# 13_BOOT_SELECT.net
KiCad netlist of a schematic drawn in Altium Designer
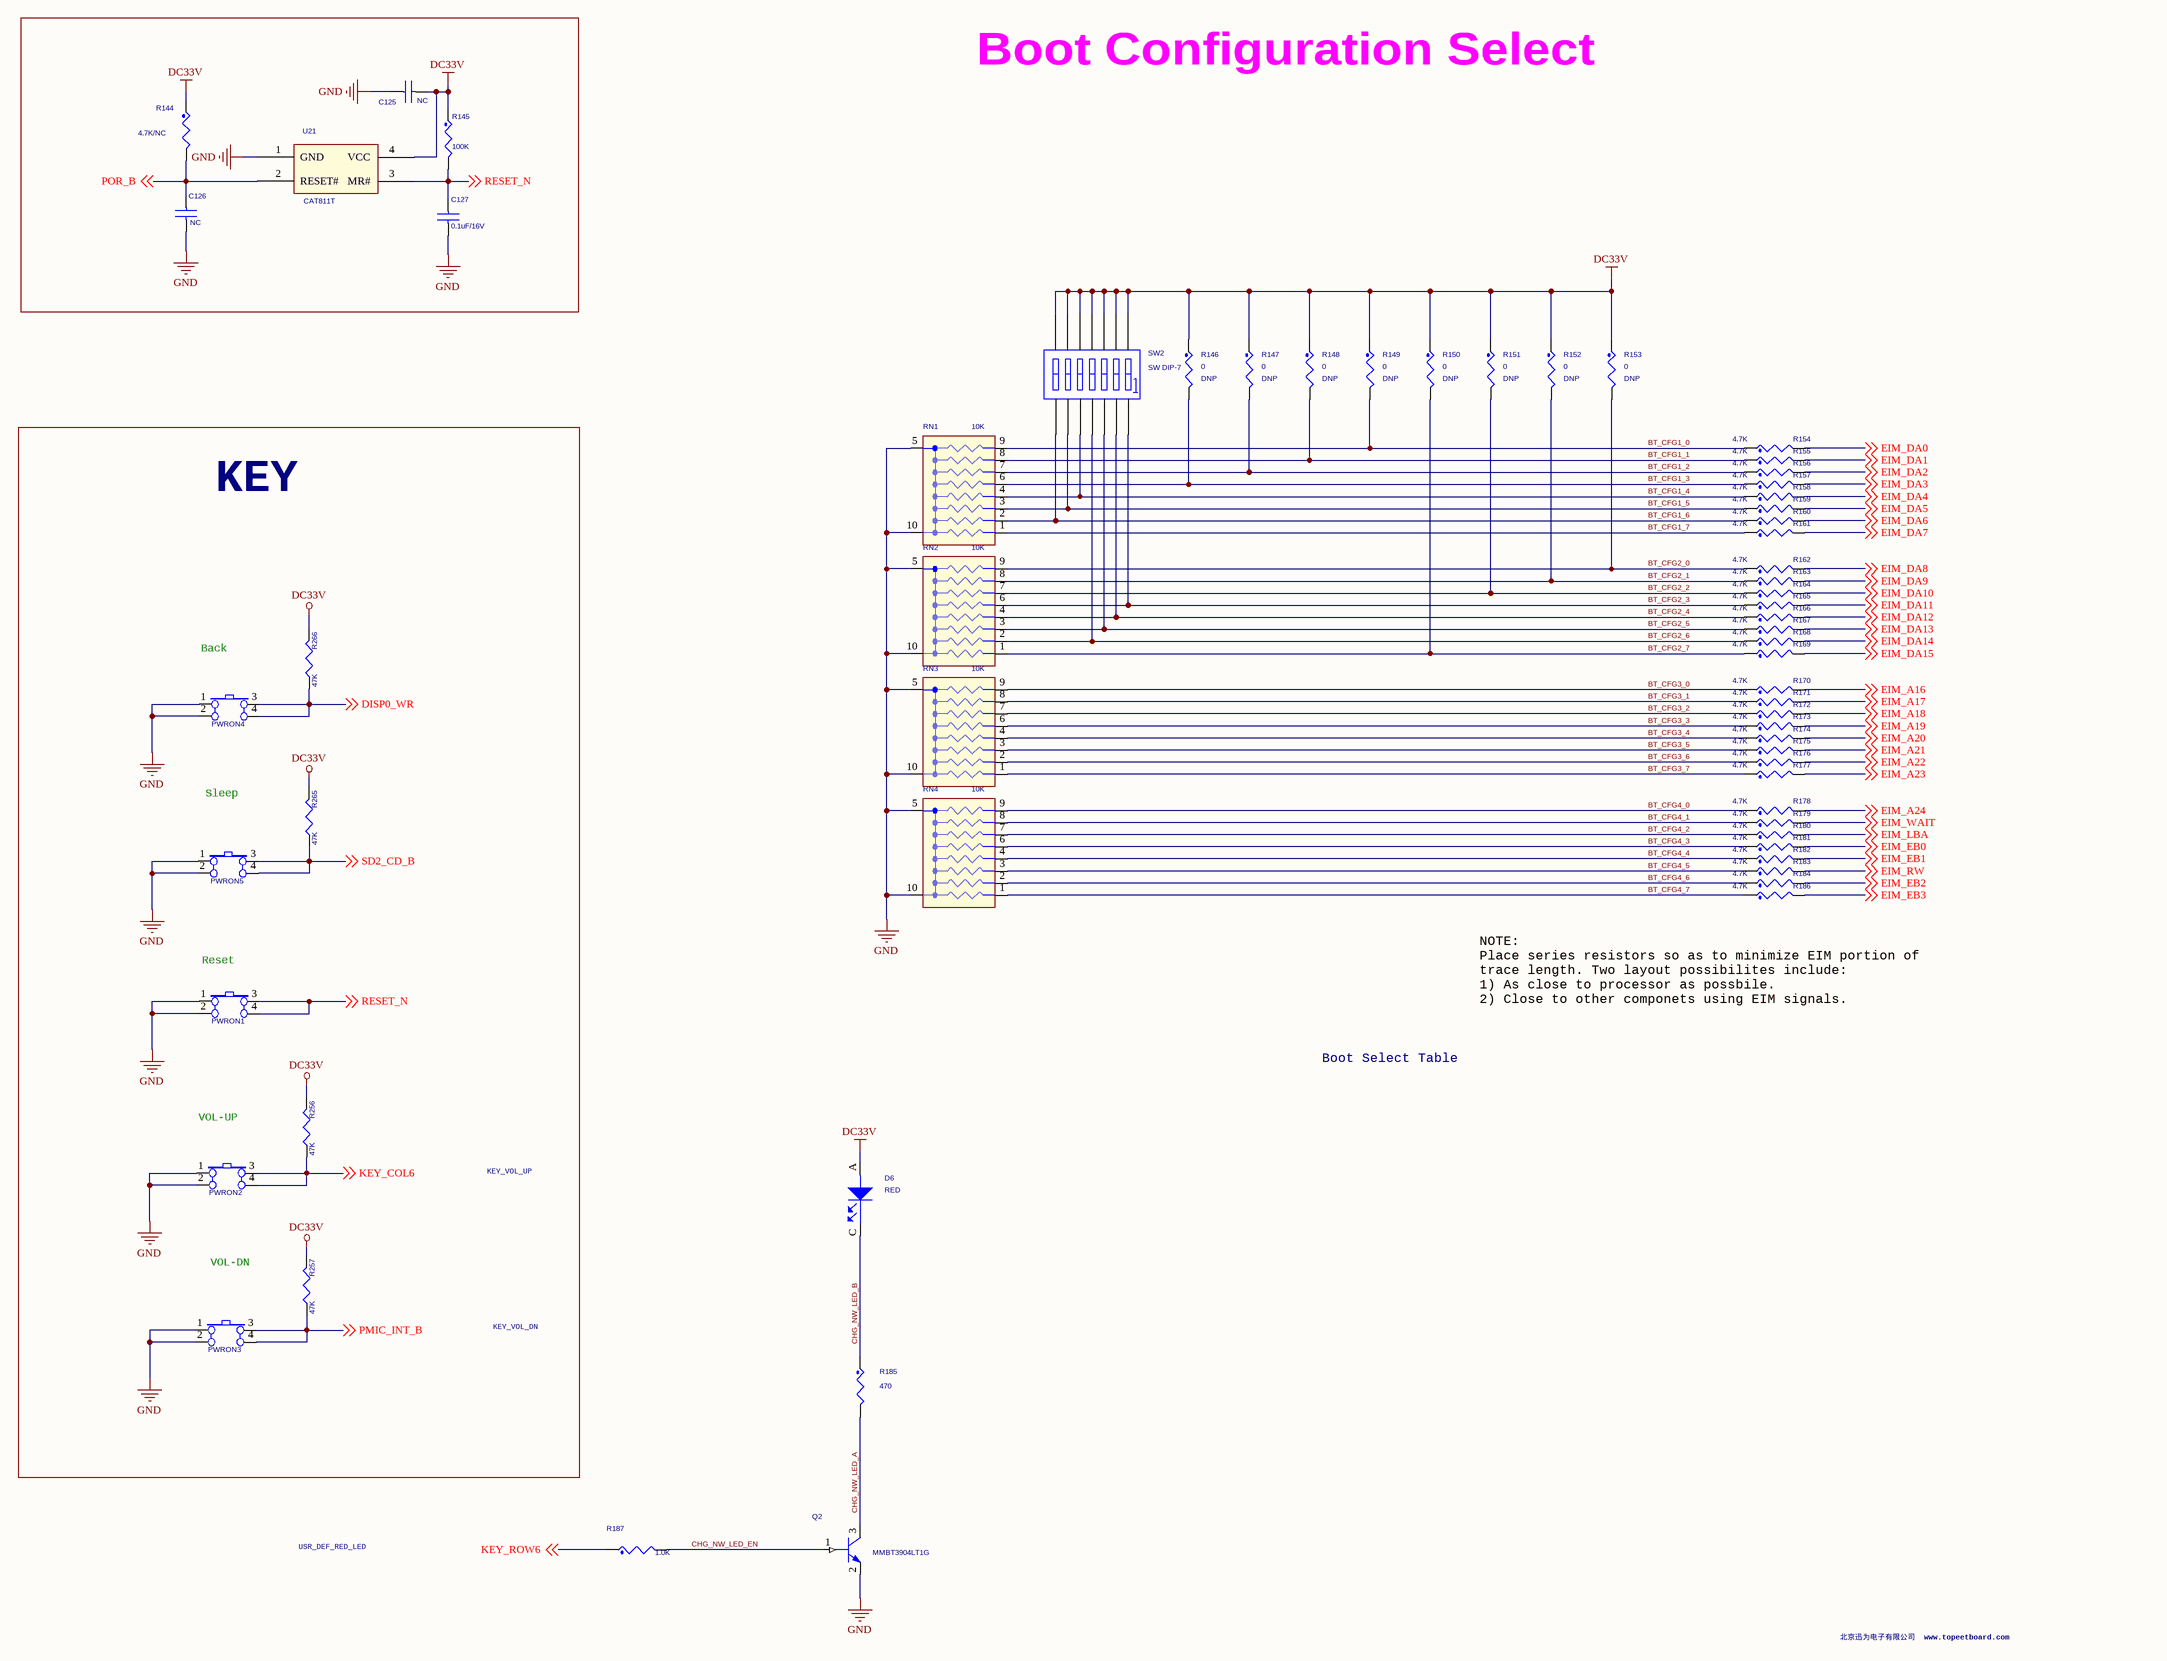
[diagram p0: 13 BOOT SELECT.SchDoc]

(export (version "E")
  (design (tool "Eeschema 10.0.6"))
  (components
    (comp (ref "C125") (value "NC") (footprint "C0603") (libsource (lib "*") (part "C0603_0_Dup1")))
    (comp (ref "C126") (value "NC") (footprint "C0603") (libsource (lib "*") (part "C0603_0_Dup1")))
    (comp (ref "C127") (value "0.1uF/16V") (footprint "C0603") (libsource (lib "*") (part "C0603_0_Dup1")))
    (comp (ref "D6")
      (value "RED")
      (description "LED ULTRA BRIGHT RED SGL 30MA 0603")
      (libsource (lib "*") (part "LED"))
    )
    (comp (ref "PWRON1")
      (value "SW-TACT(RED)_1105S")
      (footprint "SW-TACT")
      (libsource (lib "*") (part "SW-TACT"))
    )
    (comp (ref "PWRON2")
      (value "SW-TACT(RED)_1105S")
      (footprint "SW-TACT")
      (libsource (lib "*") (part "SW-TACT"))
    )
    (comp (ref "PWRON3")
      (value "SW-TACT(RED)_1105S")
      (footprint "SW-TACT")
      (libsource (lib "*") (part "SW-TACT"))
    )
    (comp (ref "PWRON4")
      (value "SW-TACT(RED)_1105S")
      (footprint "SW-TACT")
      (libsource (lib "*") (part "SW-TACT"))
    )
    (comp (ref "PWRON5")
      (value "SW-TACT(RED)_1105S")
      (footprint "SW-TACT")
      (libsource (lib "*") (part "SW-TACT"))
    )
    (comp (ref "Q2")
      (value "MMBT3904LT1G")
      (description "TRAN NPN GEN 200MA 40V SOT-23")
      (libsource (lib "*") (part "NPN"))
    )
    (comp (ref "R144")
      (value "4.7K/NC")
      (description "RES MF 470 OHM 1/10W 1% 0603")
      (fields (field (name "TOLERANCE") "1%"))
      (libsource (lib "*") (part "RES_Dup1"))
    )
    (comp (ref "R145")
      (value "100K")
      (description "RES MF 470 OHM 1/10W 1% 0603")
      (fields (field (name "TOLERANCE") "1%"))
      (libsource (lib "*") (part "RES_Dup1"))
    )
    (comp (ref "R146")
      (value "0")
      (description "RES MF ZERO OHM 1/10W -- 0402")
      (fields (field (name "ASSY_OPT") "DNP"))
      (libsource (lib "*") (part "RES_Dup1"))
    )
    (comp (ref "R147")
      (value "0")
      (description "RES MF ZERO OHM 1/10W -- 0402")
      (fields (field (name "ASSY_OPT") "DNP"))
      (libsource (lib "*") (part "RES_Dup1"))
    )
    (comp (ref "R148")
      (value "0")
      (description "RES MF ZERO OHM 1/10W -- 0402")
      (fields (field (name "ASSY_OPT") "DNP"))
      (libsource (lib "*") (part "RES_Dup1"))
    )
    (comp (ref "R149")
      (value "0")
      (description "RES MF ZERO OHM 1/10W -- 0402")
      (fields (field (name "ASSY_OPT") "DNP"))
      (libsource (lib "*") (part "RES_Dup1"))
    )
    (comp (ref "R150")
      (value "0")
      (description "RES MF ZERO OHM 1/10W -- 0402")
      (fields (field (name "ASSY_OPT") "DNP"))
      (libsource (lib "*") (part "RES_Dup1"))
    )
    (comp (ref "R151")
      (value "0")
      (description "RES MF ZERO OHM 1/10W -- 0402")
      (fields (field (name "ASSY_OPT") "DNP"))
      (libsource (lib "*") (part "RES_Dup1"))
    )
    (comp (ref "R152")
      (value "0")
      (description "RES MF ZERO OHM 1/10W -- 0402")
      (fields (field (name "ASSY_OPT") "DNP"))
      (libsource (lib "*") (part "RES_Dup1"))
    )
    (comp (ref "R153")
      (value "0")
      (description "RES MF ZERO OHM 1/10W -- 0402")
      (fields (field (name "ASSY_OPT") "DNP"))
      (libsource (lib "*") (part "RES_Dup1"))
    )
    (comp (ref "R154")
      (value "4.7K")
      (description "RES MF 4.70K 1/16W 1% 0402")
      (fields (field (name "TOLERANCE") "1%"))
      (libsource (lib "*") (part "RES_Dup1"))
    )
    (comp (ref "R155")
      (value "4.7K")
      (description "RES MF 4.70K 1/16W 1% 0402")
      (fields (field (name "TOLERANCE") "1%"))
      (libsource (lib "*") (part "RES_Dup1"))
    )
    (comp (ref "R156")
      (value "4.7K")
      (description "RES MF 4.70K 1/16W 1% 0402")
      (fields (field (name "TOLERANCE") "1%"))
      (libsource (lib "*") (part "RES_Dup1"))
    )
    (comp (ref "R157")
      (value "4.7K")
      (description "RES MF 4.70K 1/16W 1% 0402")
      (fields (field (name "TOLERANCE") "1%"))
      (libsource (lib "*") (part "RES_Dup1"))
    )
    (comp (ref "R158")
      (value "4.7K")
      (description "RES MF 4.70K 1/16W 1% 0402")
      (fields (field (name "TOLERANCE") "1%"))
      (libsource (lib "*") (part "RES_Dup1"))
    )
    (comp (ref "R159")
      (value "4.7K")
      (description "RES MF 4.70K 1/16W 1% 0402")
      (fields (field (name "TOLERANCE") "1%"))
      (libsource (lib "*") (part "RES_Dup1"))
    )
    (comp (ref "R160")
      (value "4.7K")
      (description "RES MF 4.70K 1/16W 1% 0402")
      (fields (field (name "TOLERANCE") "1%"))
      (libsource (lib "*") (part "RES_Dup1"))
    )
    (comp (ref "R161")
      (value "4.7K")
      (description "RES MF 4.70K 1/16W 1% 0402")
      (fields (field (name "TOLERANCE") "1%"))
      (libsource (lib "*") (part "RES_Dup1"))
    )
    (comp (ref "R162")
      (value "4.7K")
      (description "RES MF 4.70K 1/16W 1% 0402")
      (fields (field (name "TOLERANCE") "1%"))
      (libsource (lib "*") (part "RES_Dup1"))
    )
    (comp (ref "R163")
      (value "4.7K")
      (description "RES MF 4.70K 1/16W 1% 0402")
      (fields (field (name "TOLERANCE") "1%"))
      (libsource (lib "*") (part "RES_Dup1"))
    )
    (comp (ref "R164")
      (value "4.7K")
      (description "RES MF 4.70K 1/16W 1% 0402")
      (fields (field (name "TOLERANCE") "1%"))
      (libsource (lib "*") (part "RES_Dup1"))
    )
    (comp (ref "R165")
      (value "4.7K")
      (description "RES MF 4.70K 1/16W 1% 0402")
      (fields (field (name "TOLERANCE") "1%"))
      (libsource (lib "*") (part "RES_Dup1"))
    )
    (comp (ref "R166")
      (value "4.7K")
      (description "RES MF 4.70K 1/16W 1% 0402")
      (fields (field (name "TOLERANCE") "1%"))
      (libsource (lib "*") (part "RES_Dup1"))
    )
    (comp (ref "R167")
      (value "4.7K")
      (description "RES MF 4.70K 1/16W 1% 0402")
      (fields (field (name "TOLERANCE") "1%"))
      (libsource (lib "*") (part "RES_Dup1"))
    )
    (comp (ref "R168")
      (value "4.7K")
      (description "RES MF 4.70K 1/16W 1% 0402")
      (fields (field (name "TOLERANCE") "1%"))
      (libsource (lib "*") (part "RES_Dup1"))
    )
    (comp (ref "R169")
      (value "4.7K")
      (description "RES MF 4.70K 1/16W 1% 0402")
      (fields (field (name "TOLERANCE") "1%"))
      (libsource (lib "*") (part "RES_Dup1"))
    )
    (comp (ref "R170")
      (value "4.7K")
      (description "RES MF 4.70K 1/16W 1% 0402")
      (fields (field (name "TOLERANCE") "1%"))
      (libsource (lib "*") (part "RES_Dup1"))
    )
    (comp (ref "R171")
      (value "4.7K")
      (description "RES MF 4.70K 1/16W 1% 0402")
      (fields (field (name "TOLERANCE") "1%"))
      (libsource (lib "*") (part "RES_Dup1"))
    )
    (comp (ref "R172")
      (value "4.7K")
      (description "RES MF 4.70K 1/16W 1% 0402")
      (fields (field (name "TOLERANCE") "1%"))
      (libsource (lib "*") (part "RES_Dup1"))
    )
    (comp (ref "R173")
      (value "4.7K")
      (description "RES MF 4.70K 1/16W 1% 0402")
      (fields (field (name "TOLERANCE") "1%"))
      (libsource (lib "*") (part "RES_Dup1"))
    )
    (comp (ref "R174")
      (value "4.7K")
      (description "RES MF 4.70K 1/16W 1% 0402")
      (fields (field (name "TOLERANCE") "1%"))
      (libsource (lib "*") (part "RES_Dup1"))
    )
    (comp (ref "R175")
      (value "4.7K")
      (description "RES MF 4.70K 1/16W 1% 0402")
      (fields (field (name "TOLERANCE") "1%"))
      (libsource (lib "*") (part "RES_Dup1"))
    )
    (comp (ref "R176")
      (value "4.7K")
      (description "RES MF 4.70K 1/16W 1% 0402")
      (fields (field (name "TOLERANCE") "1%"))
      (libsource (lib "*") (part "RES_Dup1"))
    )
    (comp (ref "R177")
      (value "4.7K")
      (description "RES MF 4.70K 1/16W 1% 0402")
      (fields (field (name "TOLERANCE") "1%"))
      (libsource (lib "*") (part "RES_Dup1"))
    )
    (comp (ref "R178")
      (value "4.7K")
      (description "RES MF 4.70K 1/16W 1% 0402")
      (fields (field (name "TOLERANCE") "1%"))
      (libsource (lib "*") (part "RES_Dup1"))
    )
    (comp (ref "R179")
      (value "4.7K")
      (description "RES MF 4.70K 1/16W 1% 0402")
      (fields (field (name "TOLERANCE") "1%"))
      (libsource (lib "*") (part "RES_Dup1"))
    )
    (comp (ref "R180")
      (value "4.7K")
      (description "RES MF 4.70K 1/16W 1% 0402")
      (fields (field (name "TOLERANCE") "1%"))
      (libsource (lib "*") (part "RES_Dup1"))
    )
    (comp (ref "R181")
      (value "4.7K")
      (description "RES MF 4.70K 1/16W 1% 0402")
      (fields (field (name "TOLERANCE") "1%"))
      (libsource (lib "*") (part "RES_Dup1"))
    )
    (comp (ref "R182")
      (value "4.7K")
      (description "RES MF 4.70K 1/16W 1% 0402")
      (fields (field (name "TOLERANCE") "1%"))
      (libsource (lib "*") (part "RES_Dup1"))
    )
    (comp (ref "R183")
      (value "4.7K")
      (description "RES MF 4.70K 1/16W 1% 0402")
      (fields (field (name "TOLERANCE") "1%"))
      (libsource (lib "*") (part "RES_Dup1"))
    )
    (comp (ref "R184")
      (value "4.7K")
      (description "RES MF 4.70K 1/16W 1% 0402")
      (fields (field (name "TOLERANCE") "1%"))
      (libsource (lib "*") (part "RES_Dup1"))
    )
    (comp (ref "R185")
      (value "470")
      (description "RES MF 470 OHM 1/10W 1% 0603")
      (fields (field (name "TOLERANCE") "1%"))
      (libsource (lib "*") (part "RES_Dup1"))
    )
    (comp (ref "R186")
      (value "4.7K")
      (description "RES MF 4.70K 1/16W 1% 0402")
      (fields (field (name "TOLERANCE") "1%"))
      (libsource (lib "*") (part "RES_Dup1"))
    )
    (comp (ref "R187")
      (value "1.0K")
      (description "RES MF 1.0K 1/16W 1% 0402")
      (fields (field (name "TOLERANCE") "1%"))
      (libsource (lib "*") (part "RES_Dup1"))
    )
    (comp (ref "R256") (value "47K") (footprint "R1005") (libsource (lib "*") (part "R1005_0_Dup2")))
    (comp (ref "R257") (value "47K") (footprint "R1005") (libsource (lib "*") (part "R1005_0_Dup2")))
    (comp (ref "R265") (value "47K") (footprint "R1005") (libsource (lib "*") (part "R1005_0_Dup2")))
    (comp (ref "R266") (value "47K") (footprint "R1005") (libsource (lib "*") (part "R1005_0_Dup2")))
    (comp (ref "RN1")
      (value "10K")
      (description "RNET BUS 8 10K 1/32W 5% SMT")
      (fields (field (name "TOLERANCE") "5%"))
      (libsource (lib "*") (part "NETW_B8_10P"))
    )
    (comp (ref "RN2")
      (value "10K")
      (description "RNET BUS 8 10K 1/32W 5% SMT")
      (fields (field (name "TOLERANCE") "5%"))
      (libsource (lib "*") (part "NETW_B8_10P"))
    )
    (comp (ref "RN3")
      (value "10K")
      (description "RNET BUS 8 10K 1/32W 5% SMT")
      (fields (field (name "TOLERANCE") "5%"))
      (libsource (lib "*") (part "NETW_B8_10P"))
    )
    (comp (ref "RN4")
      (value "10K")
      (description "RNET BUS 8 10K 1/32W 5% SMT")
      (fields (field (name "TOLERANCE") "5%"))
      (libsource (lib "*") (part "NETW_B8_10P"))
    )
    (comp (ref "SW2") (value "SW DIP-7") (libsource (lib "*") (part "SW DIP-7")))
    (comp (ref "U21") (value "CAT811T") (libsource (lib "*") (part "CAT811T")))
  )
  (nets
    (net (code "1") (name "/BT_CFG1_0") (class "Default")
      (node (ref "R149") (pin "2") (pinfunction "2_2") (pintype "passive"))
      (node (ref "R154") (pin "1") (pinfunction "1_1") (pintype "passive"))
      (node (ref "RN1") (pin "9") (pinfunction "9_9") (pintype "passive"))
    )
    (net (code "2") (name "/BT_CFG1_1") (class "Default")
      (node (ref "R148") (pin "2") (pinfunction "2_2") (pintype "passive"))
      (node (ref "R155") (pin "1") (pinfunction "1_1") (pintype "passive"))
      (node (ref "RN1") (pin "8") (pinfunction "8_8") (pintype "passive"))
    )
    (net (code "3") (name "/BT_CFG1_2") (class "Default")
      (node (ref "R147") (pin "2") (pinfunction "2_2") (pintype "passive"))
      (node (ref "R156") (pin "1") (pinfunction "1_1") (pintype "passive"))
      (node (ref "RN1") (pin "7") (pinfunction "7_7") (pintype "passive"))
    )
    (net (code "4") (name "/BT_CFG1_3") (class "Default")
      (node (ref "R146") (pin "2") (pinfunction "2_2") (pintype "passive"))
      (node (ref "R157") (pin "1") (pinfunction "1_1") (pintype "passive"))
      (node (ref "RN1") (pin "6") (pinfunction "6_6") (pintype "passive"))
    )
    (net (code "5") (name "/BT_CFG1_4") (class "Default")
      (node (ref "R158") (pin "1") (pinfunction "1_1") (pintype "passive"))
      (node (ref "RN1") (pin "4") (pinfunction "4_4") (pintype "passive"))
      (node (ref "SW2") (pin "10") (pinfunction "B5_10") (pintype "passive"))
    )
    (net (code "6") (name "/BT_CFG1_5") (class "Default")
      (node (ref "R159") (pin "1") (pinfunction "1_1") (pintype "passive"))
      (node (ref "RN1") (pin "3") (pinfunction "3_3") (pintype "passive"))
      (node (ref "SW2") (pin "9") (pinfunction "B6_9") (pintype "passive"))
    )
    (net (code "7") (name "/BT_CFG1_6") (class "Default")
      (node (ref "R160") (pin "1") (pinfunction "1_1") (pintype "passive"))
      (node (ref "RN1") (pin "2") (pinfunction "2_2") (pintype "passive"))
      (node (ref "SW2") (pin "8") (pinfunction "B7_8") (pintype "passive"))
    )
    (net (code "8") (name "/BT_CFG1_7") (class "Default")
      (node (ref "R161") (pin "1") (pinfunction "1_1") (pintype "passive"))
      (node (ref "RN1") (pin "1") (pinfunction "1_1") (pintype "passive"))
    )
    (net (code "9") (name "/BT_CFG2_0") (class "Default")
      (node (ref "R153") (pin "2") (pinfunction "2_2") (pintype "passive"))
      (node (ref "R162") (pin "1") (pinfunction "1_1") (pintype "passive"))
      (node (ref "RN2") (pin "9") (pinfunction "9_9") (pintype "passive"))
    )
    (net (code "10") (name "/BT_CFG2_1") (class "Default")
      (node (ref "R152") (pin "2") (pinfunction "2_2") (pintype "passive"))
      (node (ref "R163") (pin "1") (pinfunction "1_1") (pintype "passive"))
      (node (ref "RN2") (pin "8") (pinfunction "8_8") (pintype "passive"))
    )
    (net (code "11") (name "/BT_CFG2_2") (class "Default")
      (node (ref "R151") (pin "2") (pinfunction "2_2") (pintype "passive"))
      (node (ref "R164") (pin "1") (pinfunction "1_1") (pintype "passive"))
      (node (ref "RN2") (pin "7") (pinfunction "7_7") (pintype "passive"))
    )
    (net (code "12") (name "/BT_CFG2_3") (class "Default")
      (node (ref "R165") (pin "1") (pinfunction "1_1") (pintype "passive"))
      (node (ref "RN2") (pin "6") (pinfunction "6_6") (pintype "passive"))
      (node (ref "SW2") (pin "14") (pinfunction "B1_14") (pintype "passive"))
    )
    (net (code "13") (name "/BT_CFG2_4") (class "Default")
      (node (ref "R166") (pin "1") (pinfunction "1_1") (pintype "passive"))
      (node (ref "RN2") (pin "4") (pinfunction "4_4") (pintype "passive"))
      (node (ref "SW2") (pin "13") (pinfunction "B2_13") (pintype "passive"))
    )
    (net (code "14") (name "/BT_CFG2_5") (class "Default")
      (node (ref "R167") (pin "1") (pinfunction "1_1") (pintype "passive"))
      (node (ref "RN2") (pin "3") (pinfunction "3_3") (pintype "passive"))
      (node (ref "SW2") (pin "12") (pinfunction "B3_12") (pintype "passive"))
    )
    (net (code "15") (name "/BT_CFG2_6") (class "Default")
      (node (ref "R168") (pin "1") (pinfunction "1_1") (pintype "passive"))
      (node (ref "RN2") (pin "2") (pinfunction "2_2") (pintype "passive"))
      (node (ref "SW2") (pin "11") (pinfunction "B4_11") (pintype "passive"))
    )
    (net (code "16") (name "/BT_CFG2_7") (class "Default")
      (node (ref "R150") (pin "2") (pinfunction "2_2") (pintype "passive"))
      (node (ref "R169") (pin "1") (pinfunction "1_1") (pintype "passive"))
      (node (ref "RN2") (pin "1") (pinfunction "1_1") (pintype "passive"))
    )
    (net (code "17") (name "/BT_CFG3_0") (class "Default")
      (node (ref "R170") (pin "1") (pinfunction "1_1") (pintype "passive"))
      (node (ref "RN3") (pin "9") (pinfunction "9_9") (pintype "passive"))
    )
    (net (code "18") (name "/BT_CFG3_1") (class "Default")
      (node (ref "R171") (pin "1") (pinfunction "1_1") (pintype "passive"))
      (node (ref "RN3") (pin "8") (pinfunction "8_8") (pintype "passive"))
    )
    (net (code "19") (name "/BT_CFG3_2") (class "Default")
      (node (ref "R172") (pin "1") (pinfunction "1_1") (pintype "passive"))
      (node (ref "RN3") (pin "7") (pinfunction "7_7") (pintype "passive"))
    )
    (net (code "20") (name "/BT_CFG3_3") (class "Default")
      (node (ref "R173") (pin "1") (pinfunction "1_1") (pintype "passive"))
      (node (ref "RN3") (pin "6") (pinfunction "6_6") (pintype "passive"))
    )
    (net (code "21") (name "/BT_CFG3_4") (class "Default")
      (node (ref "R174") (pin "1") (pinfunction "1_1") (pintype "passive"))
      (node (ref "RN3") (pin "4") (pinfunction "4_4") (pintype "passive"))
    )
    (net (code "22") (name "/BT_CFG3_5") (class "Default")
      (node (ref "R175") (pin "1") (pinfunction "1_1") (pintype "passive"))
      (node (ref "RN3") (pin "3") (pinfunction "3_3") (pintype "passive"))
    )
    (net (code "23") (name "/BT_CFG3_6") (class "Default")
      (node (ref "R176") (pin "1") (pinfunction "1_1") (pintype "passive"))
      (node (ref "RN3") (pin "2") (pinfunction "2_2") (pintype "passive"))
    )
    (net (code "24") (name "/BT_CFG3_7") (class "Default")
      (node (ref "R177") (pin "1") (pinfunction "1_1") (pintype "passive"))
      (node (ref "RN3") (pin "1") (pinfunction "1_1") (pintype "passive"))
    )
    (net (code "25") (name "/BT_CFG4_0") (class "Default")
      (node (ref "R178") (pin "1") (pinfunction "1_1") (pintype "passive"))
      (node (ref "RN4") (pin "9") (pinfunction "9_9") (pintype "passive"))
    )
    (net (code "26") (name "/BT_CFG4_1") (class "Default")
      (node (ref "R179") (pin "1") (pinfunction "1_1") (pintype "passive"))
      (node (ref "RN4") (pin "8") (pinfunction "8_8") (pintype "passive"))
    )
    (net (code "27") (name "/BT_CFG4_2") (class "Default")
      (node (ref "R180") (pin "1") (pinfunction "1_1") (pintype "passive"))
      (node (ref "RN4") (pin "7") (pinfunction "7_7") (pintype "passive"))
    )
    (net (code "28") (name "/BT_CFG4_3") (class "Default")
      (node (ref "R181") (pin "1") (pinfunction "1_1") (pintype "passive"))
      (node (ref "RN4") (pin "6") (pinfunction "6_6") (pintype "passive"))
    )
    (net (code "29") (name "/BT_CFG4_4") (class "Default")
      (node (ref "R182") (pin "1") (pinfunction "1_1") (pintype "passive"))
      (node (ref "RN4") (pin "4") (pinfunction "4_4") (pintype "passive"))
    )
    (net (code "30") (name "/BT_CFG4_5") (class "Default")
      (node (ref "R183") (pin "1") (pinfunction "1_1") (pintype "passive"))
      (node (ref "RN4") (pin "3") (pinfunction "3_3") (pintype "passive"))
    )
    (net (code "31") (name "/BT_CFG4_6") (class "Default")
      (node (ref "R184") (pin "1") (pinfunction "1_1") (pintype "passive"))
      (node (ref "RN4") (pin "2") (pinfunction "2_2") (pintype "passive"))
    )
    (net (code "32") (name "/BT_CFG4_7") (class "Default")
      (node (ref "R186") (pin "1") (pinfunction "1_1") (pintype "passive"))
      (node (ref "RN4") (pin "1") (pinfunction "1_1") (pintype "passive"))
    )
    (net (code "33") (name "/CHG_NW_LED_A") (class "Default")
      (node (ref "Q2") (pin "3") (pinfunction "COLLECTOR_3") (pintype "passive"))
      (node (ref "R185") (pin "2") (pinfunction "2_2") (pintype "passive"))
    )
    (net (code "34") (name "/CHG_NW_LED_B") (class "Default")
      (node (ref "D6") (pin "C") (pinfunction "CATHODE_C") (pintype "passive"))
      (node (ref "R185") (pin "1") (pinfunction "1_1") (pintype "passive"))
    )
    (net (code "35") (name "/CHG_NW_LED_EN") (class "Default")
      (node (ref "Q2") (pin "1") (pinfunction "BASE_1") (pintype "input"))
      (node (ref "R187") (pin "2") (pinfunction "2_2") (pintype "passive"))
    )
    (net (code "36") (name "DC33V") (class "Default")
      (node (ref "C125") (pin "2") (pinfunction "2_2") (pintype "passive"))
      (node (ref "D6") (pin "A") (pinfunction "ANODE_A") (pintype "passive"))
      (node (ref "R144") (pin "1") (pinfunction "1_1") (pintype "passive"))
      (node (ref "R145") (pin "1") (pinfunction "1_1") (pintype "passive"))
      (node (ref "R146") (pin "1") (pinfunction "1_1") (pintype "passive"))
      (node (ref "R147") (pin "1") (pinfunction "1_1") (pintype "passive"))
      (node (ref "R148") (pin "1") (pinfunction "1_1") (pintype "passive"))
      (node (ref "R149") (pin "1") (pinfunction "1_1") (pintype "passive"))
      (node (ref "R150") (pin "1") (pinfunction "1_1") (pintype "passive"))
      (node (ref "R151") (pin "1") (pinfunction "1_1") (pintype "passive"))
      (node (ref "R152") (pin "1") (pinfunction "1_1") (pintype "passive"))
      (node (ref "R153") (pin "1") (pinfunction "1_1") (pintype "passive"))
      (node (ref "R256") (pin "2") (pinfunction "2_2") (pintype "passive"))
      (node (ref "R257") (pin "2") (pinfunction "2_2") (pintype "passive"))
      (node (ref "R265") (pin "2") (pinfunction "2_2") (pintype "passive"))
      (node (ref "R266") (pin "2") (pinfunction "2_2") (pintype "passive"))
      (node (ref "SW2") (pin "1") (pinfunction "A1_1") (pintype "passive"))
      (node (ref "SW2") (pin "2") (pinfunction "A2_2") (pintype "passive"))
      (node (ref "SW2") (pin "3") (pinfunction "A3_3") (pintype "passive"))
      (node (ref "SW2") (pin "4") (pinfunction "A4_4") (pintype "passive"))
      (node (ref "SW2") (pin "5") (pinfunction "A5_5") (pintype "passive"))
      (node (ref "SW2") (pin "6") (pinfunction "A6_6") (pintype "passive"))
      (node (ref "SW2") (pin "7") (pinfunction "A7_7") (pintype "passive"))
      (node (ref "U21") (pin "4") (pinfunction "VCC_4") (pintype "passive"))
    )
    (net (code "37") (name "DISP0_WR") (class "Default")
      (node (ref "PWRON4") (pin "3") (pinfunction "1_3") (pintype "passive"))
      (node (ref "PWRON4") (pin "4") (pinfunction "I1_4") (pintype "passive"))
      (node (ref "R266") (pin "1") (pinfunction "1_1") (pintype "passive"))
    )
    (net (code "38") (name "EIM_A16") (class "Default")
      (node (ref "R170") (pin "2") (pinfunction "2_2") (pintype "passive"))
    )
    (net (code "39") (name "EIM_A17") (class "Default")
      (node (ref "R171") (pin "2") (pinfunction "2_2") (pintype "passive"))
    )
    (net (code "40") (name "EIM_A18") (class "Default")
      (node (ref "R172") (pin "2") (pinfunction "2_2") (pintype "passive"))
    )
    (net (code "41") (name "EIM_A19") (class "Default")
      (node (ref "R173") (pin "2") (pinfunction "2_2") (pintype "passive"))
    )
    (net (code "42") (name "EIM_A20") (class "Default")
      (node (ref "R174") (pin "2") (pinfunction "2_2") (pintype "passive"))
    )
    (net (code "43") (name "EIM_A21") (class "Default")
      (node (ref "R175") (pin "2") (pinfunction "2_2") (pintype "passive"))
    )
    (net (code "44") (name "EIM_A22") (class "Default")
      (node (ref "R176") (pin "2") (pinfunction "2_2") (pintype "passive"))
    )
    (net (code "45") (name "EIM_A23") (class "Default")
      (node (ref "R177") (pin "2") (pinfunction "2_2") (pintype "passive"))
    )
    (net (code "46") (name "EIM_A24") (class "Default")
      (node (ref "R178") (pin "2") (pinfunction "2_2") (pintype "passive"))
    )
    (net (code "47") (name "EIM_DA0") (class "Default")
      (node (ref "R154") (pin "2") (pinfunction "2_2") (pintype "passive"))
    )
    (net (code "48") (name "EIM_DA1") (class "Default")
      (node (ref "R155") (pin "2") (pinfunction "2_2") (pintype "passive"))
    )
    (net (code "49") (name "EIM_DA2") (class "Default")
      (node (ref "R156") (pin "2") (pinfunction "2_2") (pintype "passive"))
    )
    (net (code "50") (name "EIM_DA3") (class "Default")
      (node (ref "R157") (pin "2") (pinfunction "2_2") (pintype "passive"))
    )
    (net (code "51") (name "EIM_DA4") (class "Default")
      (node (ref "R158") (pin "2") (pinfunction "2_2") (pintype "passive"))
    )
    (net (code "52") (name "EIM_DA5") (class "Default")
      (node (ref "R159") (pin "2") (pinfunction "2_2") (pintype "passive"))
    )
    (net (code "53") (name "EIM_DA6") (class "Default")
      (node (ref "R160") (pin "2") (pinfunction "2_2") (pintype "passive"))
    )
    (net (code "54") (name "EIM_DA7") (class "Default")
      (node (ref "R161") (pin "2") (pinfunction "2_2") (pintype "passive"))
    )
    (net (code "55") (name "EIM_DA8") (class "Default")
      (node (ref "R162") (pin "2") (pinfunction "2_2") (pintype "passive"))
    )
    (net (code "56") (name "EIM_DA9") (class "Default")
      (node (ref "R163") (pin "2") (pinfunction "2_2") (pintype "passive"))
    )
    (net (code "57") (name "EIM_DA10") (class "Default")
      (node (ref "R164") (pin "2") (pinfunction "2_2") (pintype "passive"))
    )
    (net (code "58") (name "EIM_DA11") (class "Default")
      (node (ref "R165") (pin "2") (pinfunction "2_2") (pintype "passive"))
    )
    (net (code "59") (name "EIM_DA12") (class "Default")
      (node (ref "R166") (pin "2") (pinfunction "2_2") (pintype "passive"))
    )
    (net (code "60") (name "EIM_DA13") (class "Default")
      (node (ref "R167") (pin "2") (pinfunction "2_2") (pintype "passive"))
    )
    (net (code "61") (name "EIM_DA14") (class "Default")
      (node (ref "R168") (pin "2") (pinfunction "2_2") (pintype "passive"))
    )
    (net (code "62") (name "EIM_DA15") (class "Default")
      (node (ref "R169") (pin "2") (pinfunction "2_2") (pintype "passive"))
    )
    (net (code "63") (name "EIM_EB0") (class "Default")
      (node (ref "R181") (pin "2") (pinfunction "2_2") (pintype "passive"))
    )
    (net (code "64") (name "EIM_EB1") (class "Default")
      (node (ref "R182") (pin "2") (pinfunction "2_2") (pintype "passive"))
    )
    (net (code "65") (name "EIM_EB2") (class "Default")
      (node (ref "R184") (pin "2") (pinfunction "2_2") (pintype "passive"))
    )
    (net (code "66") (name "EIM_EB3") (class "Default")
      (node (ref "R186") (pin "2") (pinfunction "2_2") (pintype "passive"))
    )
    (net (code "67") (name "EIM_LBA") (class "Default")
      (node (ref "R180") (pin "2") (pinfunction "2_2") (pintype "passive"))
    )
    (net (code "68") (name "EIM_RW") (class "Default")
      (node (ref "R183") (pin "2") (pinfunction "2_2") (pintype "passive"))
    )
    (net (code "69") (name "EIM_WAIT") (class "Default")
      (node (ref "R179") (pin "2") (pinfunction "2_2") (pintype "passive"))
    )
    (net (code "70") (name "GND") (class "Default")
      (node (ref "C125") (pin "1") (pinfunction "1_1") (pintype "passive"))
      (node (ref "C126") (pin "2") (pinfunction "2_2") (pintype "passive"))
      (node (ref "C127") (pin "2") (pinfunction "2_2") (pintype "passive"))
      (node (ref "PWRON1") (pin "1") (pinfunction "I2_1") (pintype "passive"))
      (node (ref "PWRON1") (pin "2") (pinfunction "I3_2") (pintype "passive"))
      (node (ref "PWRON2") (pin "1") (pinfunction "I2_1") (pintype "passive"))
      (node (ref "PWRON2") (pin "2") (pinfunction "I3_2") (pintype "passive"))
      (node (ref "PWRON3") (pin "1") (pinfunction "I2_1") (pintype "passive"))
      (node (ref "PWRON3") (pin "2") (pinfunction "I3_2") (pintype "passive"))
      (node (ref "PWRON4") (pin "1") (pinfunction "I2_1") (pintype "passive"))
      (node (ref "PWRON4") (pin "2") (pinfunction "I3_2") (pintype "passive"))
      (node (ref "PWRON5") (pin "1") (pinfunction "I2_1") (pintype "passive"))
      (node (ref "PWRON5") (pin "2") (pinfunction "I3_2") (pintype "passive"))
      (node (ref "Q2") (pin "2") (pinfunction "EMITTER_2") (pintype "passive"))
      (node (ref "RN1") (pin "10") (pinfunction "10_10") (pintype "passive"))
      (node (ref "RN1") (pin "5") (pinfunction "5_5") (pintype "passive"))
      (node (ref "RN2") (pin "10") (pinfunction "10_10") (pintype "passive"))
      (node (ref "RN2") (pin "5") (pinfunction "5_5") (pintype "passive"))
      (node (ref "RN3") (pin "10") (pinfunction "10_10") (pintype "passive"))
      (node (ref "RN3") (pin "5") (pinfunction "5_5") (pintype "passive"))
      (node (ref "RN4") (pin "10") (pinfunction "10_10") (pintype "passive"))
      (node (ref "RN4") (pin "5") (pinfunction "5_5") (pintype "passive"))
      (node (ref "U21") (pin "1") (pinfunction "GND_1") (pintype "passive"))
    )
    (net (code "71") (name "KEY_COL6") (class "Default")
      (node (ref "PWRON2") (pin "3") (pinfunction "1_3") (pintype "passive"))
      (node (ref "PWRON2") (pin "4") (pinfunction "I1_4") (pintype "passive"))
      (node (ref "R256") (pin "1") (pinfunction "1_1") (pintype "passive"))
    )
    (net (code "72") (name "KEY_ROW6") (class "Default")
      (node (ref "R187") (pin "1") (pinfunction "1_1") (pintype "passive"))
    )
    (net (code "73") (name "PMIC_INT_B") (class "Default")
      (node (ref "PWRON3") (pin "3") (pinfunction "1_3") (pintype "passive"))
      (node (ref "PWRON3") (pin "4") (pinfunction "I1_4") (pintype "passive"))
      (node (ref "R257") (pin "1") (pinfunction "1_1") (pintype "passive"))
    )
    (net (code "74") (name "POR_B") (class "Default")
      (node (ref "C126") (pin "1") (pinfunction "1_1") (pintype "passive"))
      (node (ref "R144") (pin "2") (pinfunction "2_2") (pintype "passive"))
      (node (ref "U21") (pin "2") (pinfunction "RESET#_2") (pintype "passive"))
    )
    (net (code "75") (name "RESET_N") (class "Default")
      (node (ref "C127") (pin "1") (pinfunction "1_1") (pintype "passive"))
      (node (ref "PWRON1") (pin "3") (pinfunction "1_3") (pintype "passive"))
      (node (ref "PWRON1") (pin "4") (pinfunction "I1_4") (pintype "passive"))
      (node (ref "R145") (pin "2") (pinfunction "2_2") (pintype "passive"))
      (node (ref "U21") (pin "3") (pinfunction "MR#_3") (pintype "passive"))
    )
    (net (code "76") (name "SD2_CD_B") (class "Default")
      (node (ref "PWRON5") (pin "3") (pinfunction "1_3") (pintype "passive"))
      (node (ref "PWRON5") (pin "4") (pinfunction "I1_4") (pintype "passive"))
      (node (ref "R265") (pin "1") (pinfunction "1_1") (pintype "passive"))
    )
  )
)
